# LED_s.net
KiCad netlist of a schematic drawn in EAGLE
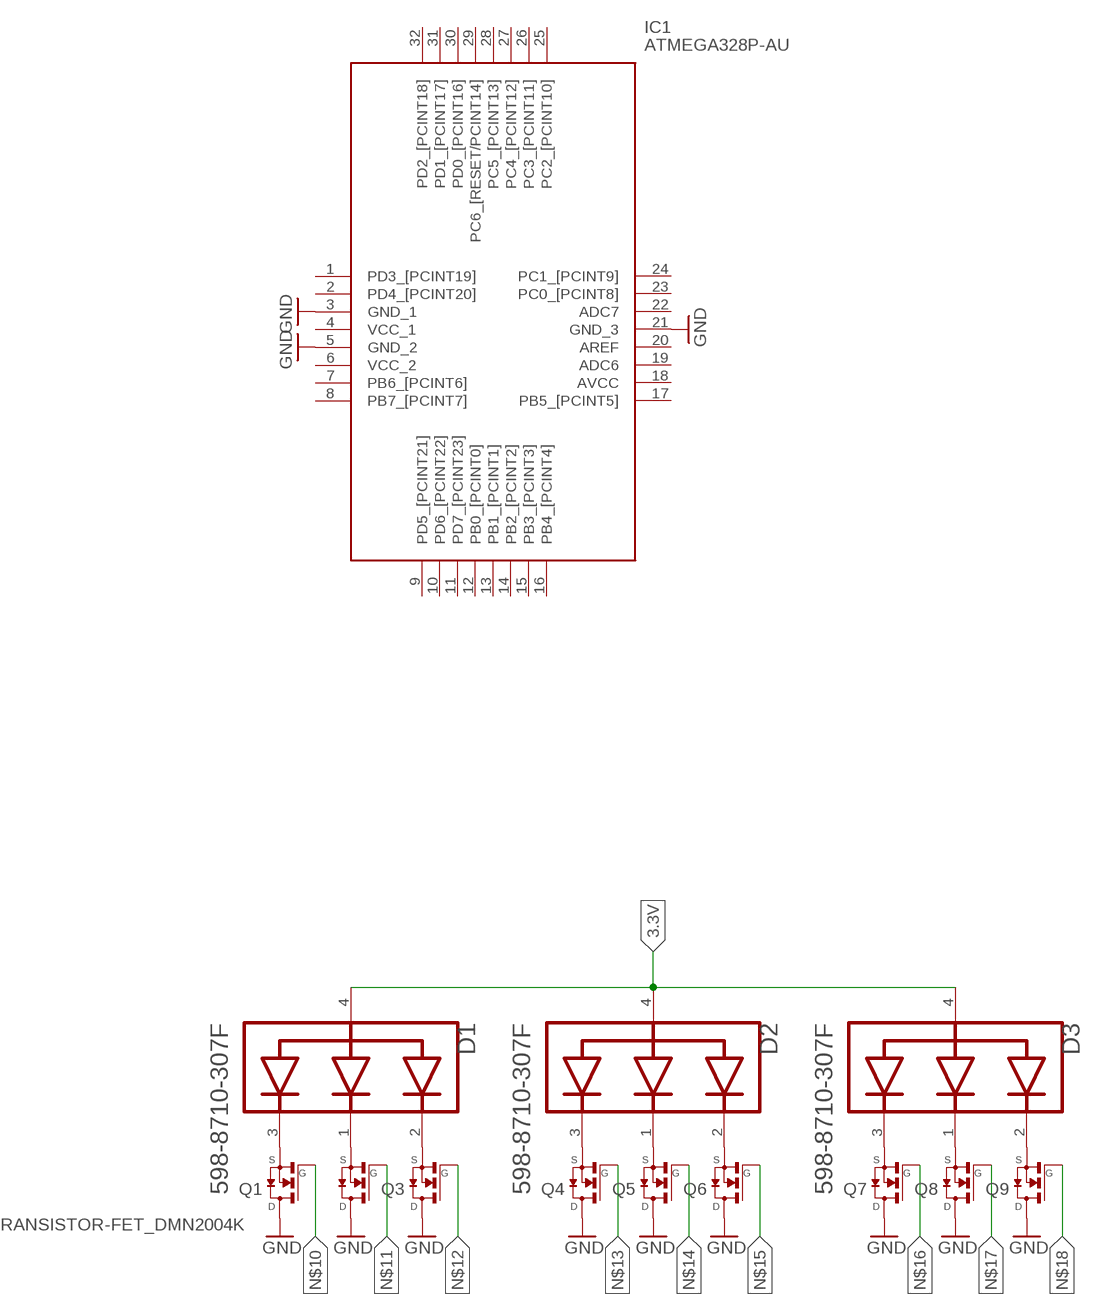
[diagram p0: schematic, sheet 1]

(export (version "E")
  (design (tool "Eeschema 10.0.6"))
  (components
    (comp (ref "D1")
      (value "DIALIGHT_598-8710-307FDIALIGHT_598-8710-307F_0_0")
      (footprint "eagle-import:DIALIGHT_598-8710-307F_0")
      (fields
        (field (name "DIGIKEY_PART_NUMBER") "350-2096-1-ND")
        (field (name "MF") "Dialight")
        (field (name "MOUSER_PART_NUMBER") "645-598-8710-307F")
      )
      (libsource (lib "eagle-import") (part "DIALIGHT_598-8710-307FDIALIGHT_598-8710-307F_0_0"))
    )
    (comp (ref "D2")
      (value "DIALIGHT_598-8710-307FDIALIGHT_598-8710-307F_0_0")
      (footprint "eagle-import:DIALIGHT_598-8710-307F_0")
      (fields
        (field (name "DIGIKEY_PART_NUMBER") "350-2096-1-ND")
        (field (name "MF") "Dialight")
        (field (name "MOUSER_PART_NUMBER") "645-598-8710-307F")
      )
      (libsource (lib "eagle-import") (part "DIALIGHT_598-8710-307FDIALIGHT_598-8710-307F_0_0"))
    )
    (comp (ref "D3")
      (value "DIALIGHT_598-8710-307FDIALIGHT_598-8710-307F_0_0")
      (footprint "eagle-import:DIALIGHT_598-8710-307F_0")
      (fields
        (field (name "DIGIKEY_PART_NUMBER") "350-2096-1-ND")
        (field (name "MF") "Dialight")
        (field (name "MOUSER_PART_NUMBER") "645-598-8710-307F")
      )
      (libsource (lib "eagle-import") (part "DIALIGHT_598-8710-307FDIALIGHT_598-8710-307F_0_0"))
    )
    (comp (ref "IC1")
      (value "ATMEGA328P-AU")
      (footprint "eagle-import:QFP80P900X900X120-32N")
      (fields
        (field (name "MOUSER_PART_NUMBER") "556-ATMEGA328P-AU")
        (field (name "RS_PART_NUMBER") "1310271P")
      )
      (libsource (lib "eagle-import") (part "ATMEGA328P-AU"))
    )
    (comp (ref "Q1")
      (value "TRANSISTOR-FET_DMN2004K")
      (footprint "eagle-import:TRANSISTOR-FET_SOT23")
      (libsource (lib "eagle-import") (part "TRANSISTOR-FET_DMN2004K"))
    )
    (comp (ref "Q2")
      (value "TRANSISTOR-FET_DMN2004K")
      (footprint "eagle-import:TRANSISTOR-FET_SOT23")
      (libsource (lib "eagle-import") (part "TRANSISTOR-FET_DMN2004K"))
    )
    (comp (ref "Q3")
      (value "TRANSISTOR-FET_DMN2004K")
      (footprint "eagle-import:TRANSISTOR-FET_SOT23")
      (libsource (lib "eagle-import") (part "TRANSISTOR-FET_DMN2004K"))
    )
    (comp (ref "Q4")
      (value "TRANSISTOR-FET_DMN2004K")
      (footprint "eagle-import:TRANSISTOR-FET_SOT23")
      (libsource (lib "eagle-import") (part "TRANSISTOR-FET_DMN2004K"))
    )
    (comp (ref "Q5")
      (value "TRANSISTOR-FET_DMN2004K")
      (footprint "eagle-import:TRANSISTOR-FET_SOT23")
      (libsource (lib "eagle-import") (part "TRANSISTOR-FET_DMN2004K"))
    )
    (comp (ref "Q6")
      (value "TRANSISTOR-FET_DMN2004K")
      (footprint "eagle-import:TRANSISTOR-FET_SOT23")
      (libsource (lib "eagle-import") (part "TRANSISTOR-FET_DMN2004K"))
    )
    (comp (ref "Q7")
      (value "TRANSISTOR-FET_DMN2004K")
      (footprint "eagle-import:TRANSISTOR-FET_SOT23")
      (libsource (lib "eagle-import") (part "TRANSISTOR-FET_DMN2004K"))
    )
    (comp (ref "Q8")
      (value "TRANSISTOR-FET_DMN2004K")
      (footprint "eagle-import:TRANSISTOR-FET_SOT23")
      (libsource (lib "eagle-import") (part "TRANSISTOR-FET_DMN2004K"))
    )
    (comp (ref "Q9")
      (value "TRANSISTOR-FET_DMN2004K")
      (footprint "eagle-import:TRANSISTOR-FET_SOT23")
      (libsource (lib "eagle-import") (part "TRANSISTOR-FET_DMN2004K"))
    )
  )
  (nets
    (net (code "1") (name "/AVCC") (class "Default")
      (node (ref "IC1") (pin "18") (pinfunction "AVCC_18") (pintype "power_in"))
    )
    (net (code "2") (name "/VCC_1") (class "Default")
      (node (ref "IC1") (pin "4") (pinfunction "VCC_1_4") (pintype "power_in"))
    )
    (net (code "3") (name "/VCC_2") (class "Default")
      (node (ref "IC1") (pin "6") (pinfunction "VCC_2_6") (pintype "power_in"))
    )
    (net (code "4") (name "3.3V") (class "Default")
      (node (ref "D1") (pin "4") (pinfunction "COMMON_ANODE_4") (pintype "bidirectional"))
      (node (ref "D2") (pin "4") (pinfunction "COMMON_ANODE_4") (pintype "bidirectional"))
      (node (ref "D3") (pin "4") (pinfunction "COMMON_ANODE_4") (pintype "bidirectional"))
    )
    (net (code "5") (name "GND") (class "Default")
      (node (ref "IC1") (pin "21") (pinfunction "GND_3_21") (pintype "power_in"))
      (node (ref "IC1") (pin "3") (pinfunction "GND_1_3") (pintype "power_in"))
      (node (ref "IC1") (pin "5") (pinfunction "GND_2_5") (pintype "power_in"))
      (node (ref "Q1") (pin "3") (pinfunction "D_3") (pintype "passive"))
      (node (ref "Q2") (pin "3") (pinfunction "D_3") (pintype "passive"))
      (node (ref "Q3") (pin "3") (pinfunction "D_3") (pintype "passive"))
      (node (ref "Q4") (pin "3") (pinfunction "D_3") (pintype "passive"))
      (node (ref "Q5") (pin "3") (pinfunction "D_3") (pintype "passive"))
      (node (ref "Q6") (pin "3") (pinfunction "D_3") (pintype "passive"))
      (node (ref "Q7") (pin "3") (pinfunction "D_3") (pintype "passive"))
      (node (ref "Q8") (pin "3") (pinfunction "D_3") (pintype "passive"))
      (node (ref "Q9") (pin "3") (pinfunction "D_3") (pintype "passive"))
    )
    (net (code "6") (name "N$10") (class "Default")
      (node (ref "Q1") (pin "1") (pinfunction "G_1") (pintype "passive"))
    )
    (net (code "7") (name "N$11") (class "Default")
      (node (ref "Q2") (pin "1") (pinfunction "G_1") (pintype "passive"))
    )
    (net (code "8") (name "N$12") (class "Default")
      (node (ref "Q3") (pin "1") (pinfunction "G_1") (pintype "passive"))
    )
    (net (code "9") (name "N$13") (class "Default")
      (node (ref "Q4") (pin "1") (pinfunction "G_1") (pintype "passive"))
    )
    (net (code "10") (name "N$14") (class "Default")
      (node (ref "Q5") (pin "1") (pinfunction "G_1") (pintype "passive"))
    )
    (net (code "11") (name "N$15") (class "Default")
      (node (ref "Q6") (pin "1") (pinfunction "G_1") (pintype "passive"))
    )
    (net (code "12") (name "N$16") (class "Default")
      (node (ref "Q7") (pin "1") (pinfunction "G_1") (pintype "passive"))
    )
    (net (code "13") (name "N$17") (class "Default")
      (node (ref "Q8") (pin "1") (pinfunction "G_1") (pintype "passive"))
    )
    (net (code "14") (name "N$18") (class "Default")
      (node (ref "Q9") (pin "1") (pinfunction "G_1") (pintype "passive"))
    )
    (net (code "15") (name "Net-(D1-BLUE_CATHODE)") (class "Default")
      (node (ref "D1") (pin "3") (pinfunction "BLUE_CATHODE_3") (pintype "bidirectional"))
      (node (ref "Q1") (pin "2") (pinfunction "S_2") (pintype "passive"))
    )
    (net (code "16") (name "Net-(D1-GREEN_CATHODE)") (class "Default")
      (node (ref "D1") (pin "1") (pinfunction "GREEN_CATHODE_1") (pintype "bidirectional"))
      (node (ref "Q2") (pin "2") (pinfunction "S_2") (pintype "passive"))
    )
    (net (code "17") (name "Net-(D1-RED_CATHODE)") (class "Default")
      (node (ref "D1") (pin "2") (pinfunction "RED_CATHODE_2") (pintype "bidirectional"))
      (node (ref "Q3") (pin "2") (pinfunction "S_2") (pintype "passive"))
    )
    (net (code "18") (name "Net-(D2-BLUE_CATHODE)") (class "Default")
      (node (ref "D2") (pin "3") (pinfunction "BLUE_CATHODE_3") (pintype "bidirectional"))
      (node (ref "Q4") (pin "2") (pinfunction "S_2") (pintype "passive"))
    )
    (net (code "19") (name "Net-(D2-GREEN_CATHODE)") (class "Default")
      (node (ref "D2") (pin "1") (pinfunction "GREEN_CATHODE_1") (pintype "bidirectional"))
      (node (ref "Q5") (pin "2") (pinfunction "S_2") (pintype "passive"))
    )
    (net (code "20") (name "Net-(D2-RED_CATHODE)") (class "Default")
      (node (ref "D2") (pin "2") (pinfunction "RED_CATHODE_2") (pintype "bidirectional"))
      (node (ref "Q6") (pin "2") (pinfunction "S_2") (pintype "passive"))
    )
    (net (code "21") (name "Net-(D3-BLUE_CATHODE)") (class "Default")
      (node (ref "D3") (pin "3") (pinfunction "BLUE_CATHODE_3") (pintype "bidirectional"))
      (node (ref "Q7") (pin "2") (pinfunction "S_2") (pintype "passive"))
    )
    (net (code "22") (name "Net-(D3-GREEN_CATHODE)") (class "Default")
      (node (ref "D3") (pin "1") (pinfunction "GREEN_CATHODE_1") (pintype "bidirectional"))
      (node (ref "Q8") (pin "2") (pinfunction "S_2") (pintype "passive"))
    )
    (net (code "23") (name "Net-(D3-RED_CATHODE)") (class "Default")
      (node (ref "D3") (pin "2") (pinfunction "RED_CATHODE_2") (pintype "bidirectional"))
      (node (ref "Q9") (pin "2") (pinfunction "S_2") (pintype "passive"))
    )
    (net (code "24") (name "unconnected-(IC1-ADC6-Pad19)") (class "Default")
      (node (ref "IC1") (pin "19") (pinfunction "ADC6_19") (pintype "bidirectional"))
    )
    (net (code "25") (name "unconnected-(IC1-ADC7-Pad22)") (class "Default")
      (node (ref "IC1") (pin "22") (pinfunction "ADC7_22") (pintype "bidirectional"))
    )
    (net (code "26") (name "unconnected-(IC1-AREF-Pad20)") (class "Default")
      (node (ref "IC1") (pin "20") (pinfunction "AREF_20") (pintype "bidirectional"))
    )
    (net (code "27") (name "unconnected-(IC1-PB0_[PCINT0]-Pad12)") (class "Default")
      (node (ref "IC1") (pin "12") (pinfunction "PB0_[PCINT0]_12") (pintype "bidirectional"))
    )
    (net (code "28") (name "unconnected-(IC1-PB1_[PCINT1]-Pad13)") (class "Default")
      (node (ref "IC1") (pin "13") (pinfunction "PB1_[PCINT1]_13") (pintype "bidirectional"))
    )
    (net (code "29") (name "unconnected-(IC1-PB2_[PCINT2]-Pad14)") (class "Default")
      (node (ref "IC1") (pin "14") (pinfunction "PB2_[PCINT2]_14") (pintype "bidirectional"))
    )
    (net (code "30") (name "unconnected-(IC1-PB3_[PCINT3]-Pad15)") (class "Default")
      (node (ref "IC1") (pin "15") (pinfunction "PB3_[PCINT3]_15") (pintype "bidirectional"))
    )
    (net (code "31") (name "unconnected-(IC1-PB4_[PCINT4]-Pad16)") (class "Default")
      (node (ref "IC1") (pin "16") (pinfunction "PB4_[PCINT4]_16") (pintype "bidirectional"))
    )
    (net (code "32") (name "unconnected-(IC1-PB5_[PCINT5]-Pad17)") (class "Default")
      (node (ref "IC1") (pin "17") (pinfunction "PB5_[PCINT5]_17") (pintype "bidirectional"))
    )
    (net (code "33") (name "unconnected-(IC1-PB6_[PCINT6]-Pad7)") (class "Default")
      (node (ref "IC1") (pin "7") (pinfunction "PB6_[PCINT6]_7") (pintype "bidirectional"))
    )
    (net (code "34") (name "unconnected-(IC1-PB7_[PCINT7]-Pad8)") (class "Default")
      (node (ref "IC1") (pin "8") (pinfunction "PB7_[PCINT7]_8") (pintype "bidirectional"))
    )
    (net (code "35") (name "unconnected-(IC1-PC0_[PCINT8]-Pad23)") (class "Default")
      (node (ref "IC1") (pin "23") (pinfunction "PC0_[PCINT8]_23") (pintype "bidirectional"))
    )
    (net (code "36") (name "unconnected-(IC1-PC1_[PCINT9]-Pad24)") (class "Default")
      (node (ref "IC1") (pin "24") (pinfunction "PC1_[PCINT9]_24") (pintype "bidirectional"))
    )
    (net (code "37") (name "unconnected-(IC1-PC2_[PCINT10]-Pad25)") (class "Default")
      (node (ref "IC1") (pin "25") (pinfunction "PC2_[PCINT10]_25") (pintype "bidirectional"))
    )
    (net (code "38") (name "unconnected-(IC1-PC3_[PCINT11]-Pad26)") (class "Default")
      (node (ref "IC1") (pin "26") (pinfunction "PC3_[PCINT11]_26") (pintype "bidirectional"))
    )
    (net (code "39") (name "unconnected-(IC1-PC4_[PCINT12]-Pad27)") (class "Default")
      (node (ref "IC1") (pin "27") (pinfunction "PC4_[PCINT12]_27") (pintype "bidirectional"))
    )
    (net (code "40") (name "unconnected-(IC1-PC5_[PCINT13]-Pad28)") (class "Default")
      (node (ref "IC1") (pin "28") (pinfunction "PC5_[PCINT13]_28") (pintype "bidirectional"))
    )
    (net (code "41") (name "unconnected-(IC1-PC6_[RESET{slash}PCINT14]-Pad29)") (class "Default")
      (node (ref "IC1") (pin "29") (pinfunction "PC6_[RESET/PCINT14]_29") (pintype "bidirectional"))
    )
    (net (code "42") (name "unconnected-(IC1-PD0_[PCINT16]-Pad30)") (class "Default")
      (node (ref "IC1") (pin "30") (pinfunction "PD0_[PCINT16]_30") (pintype "bidirectional"))
    )
    (net (code "43") (name "unconnected-(IC1-PD1_[PCINT17]-Pad31)") (class "Default")
      (node (ref "IC1") (pin "31") (pinfunction "PD1_[PCINT17]_31") (pintype "bidirectional"))
    )
    (net (code "44") (name "unconnected-(IC1-PD2_[PCINT18]-Pad32)") (class "Default")
      (node (ref "IC1") (pin "32") (pinfunction "PD2_[PCINT18]_32") (pintype "bidirectional"))
    )
    (net (code "45") (name "unconnected-(IC1-PD3_[PCINT19]-Pad1)") (class "Default")
      (node (ref "IC1") (pin "1") (pinfunction "PD3_[PCINT19]_1") (pintype "bidirectional"))
    )
    (net (code "46") (name "unconnected-(IC1-PD4_[PCINT20]-Pad2)") (class "Default")
      (node (ref "IC1") (pin "2") (pinfunction "PD4_[PCINT20]_2") (pintype "bidirectional"))
    )
    (net (code "47") (name "unconnected-(IC1-PD5_[PCINT21]-Pad9)") (class "Default")
      (node (ref "IC1") (pin "9") (pinfunction "PD5_[PCINT21]_9") (pintype "bidirectional"))
    )
    (net (code "48") (name "unconnected-(IC1-PD6_[PCINT22]-Pad10)") (class "Default")
      (node (ref "IC1") (pin "10") (pinfunction "PD6_[PCINT22]_10") (pintype "bidirectional"))
    )
    (net (code "49") (name "unconnected-(IC1-PD7_[PCINT23]-Pad11)") (class "Default")
      (node (ref "IC1") (pin "11") (pinfunction "PD7_[PCINT23]_11") (pintype "bidirectional"))
    )
  )
)
